# InkTime_Schematic.net
KiCad netlist of a schematic drawn in EAGLE
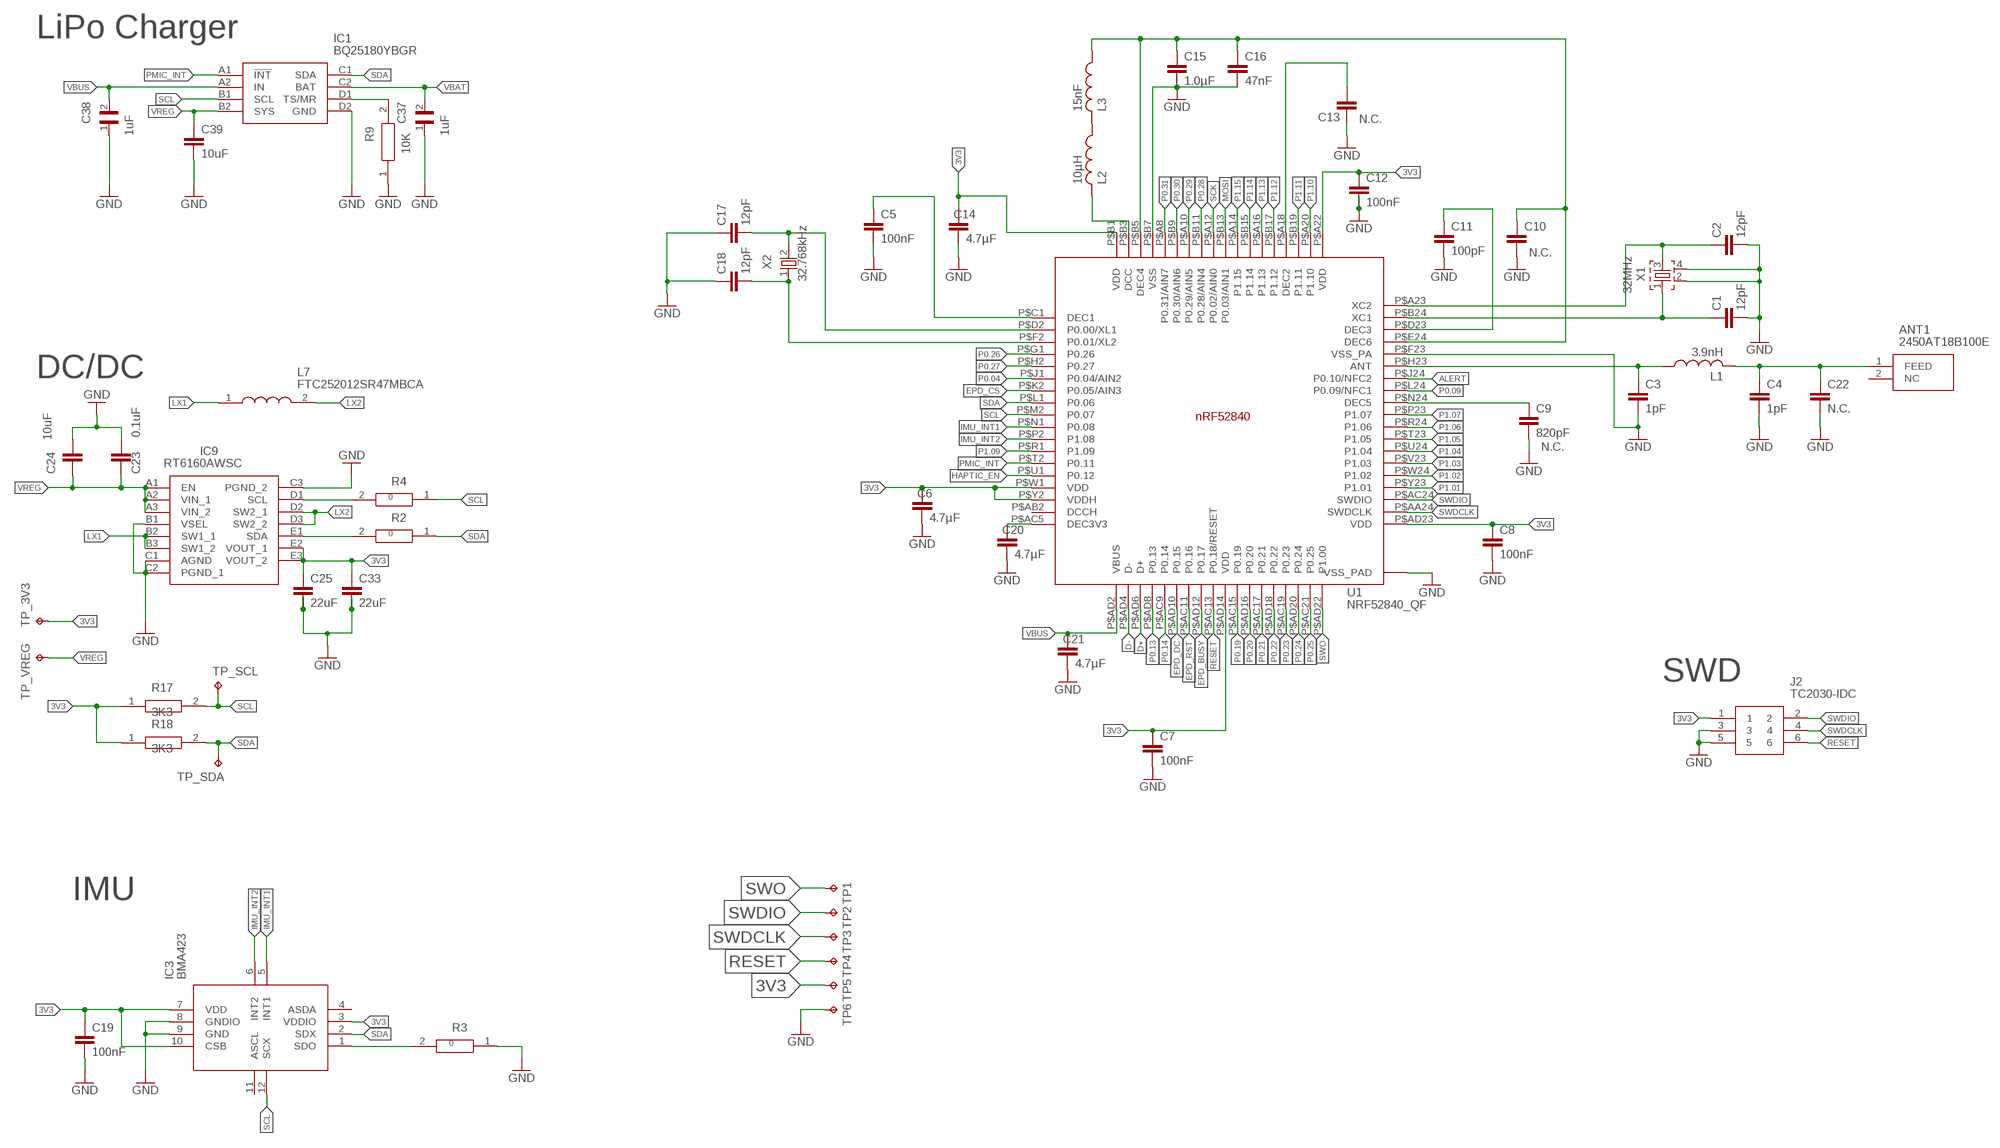
[diagram p0: schematic, sheet 1, part 1 of 2]
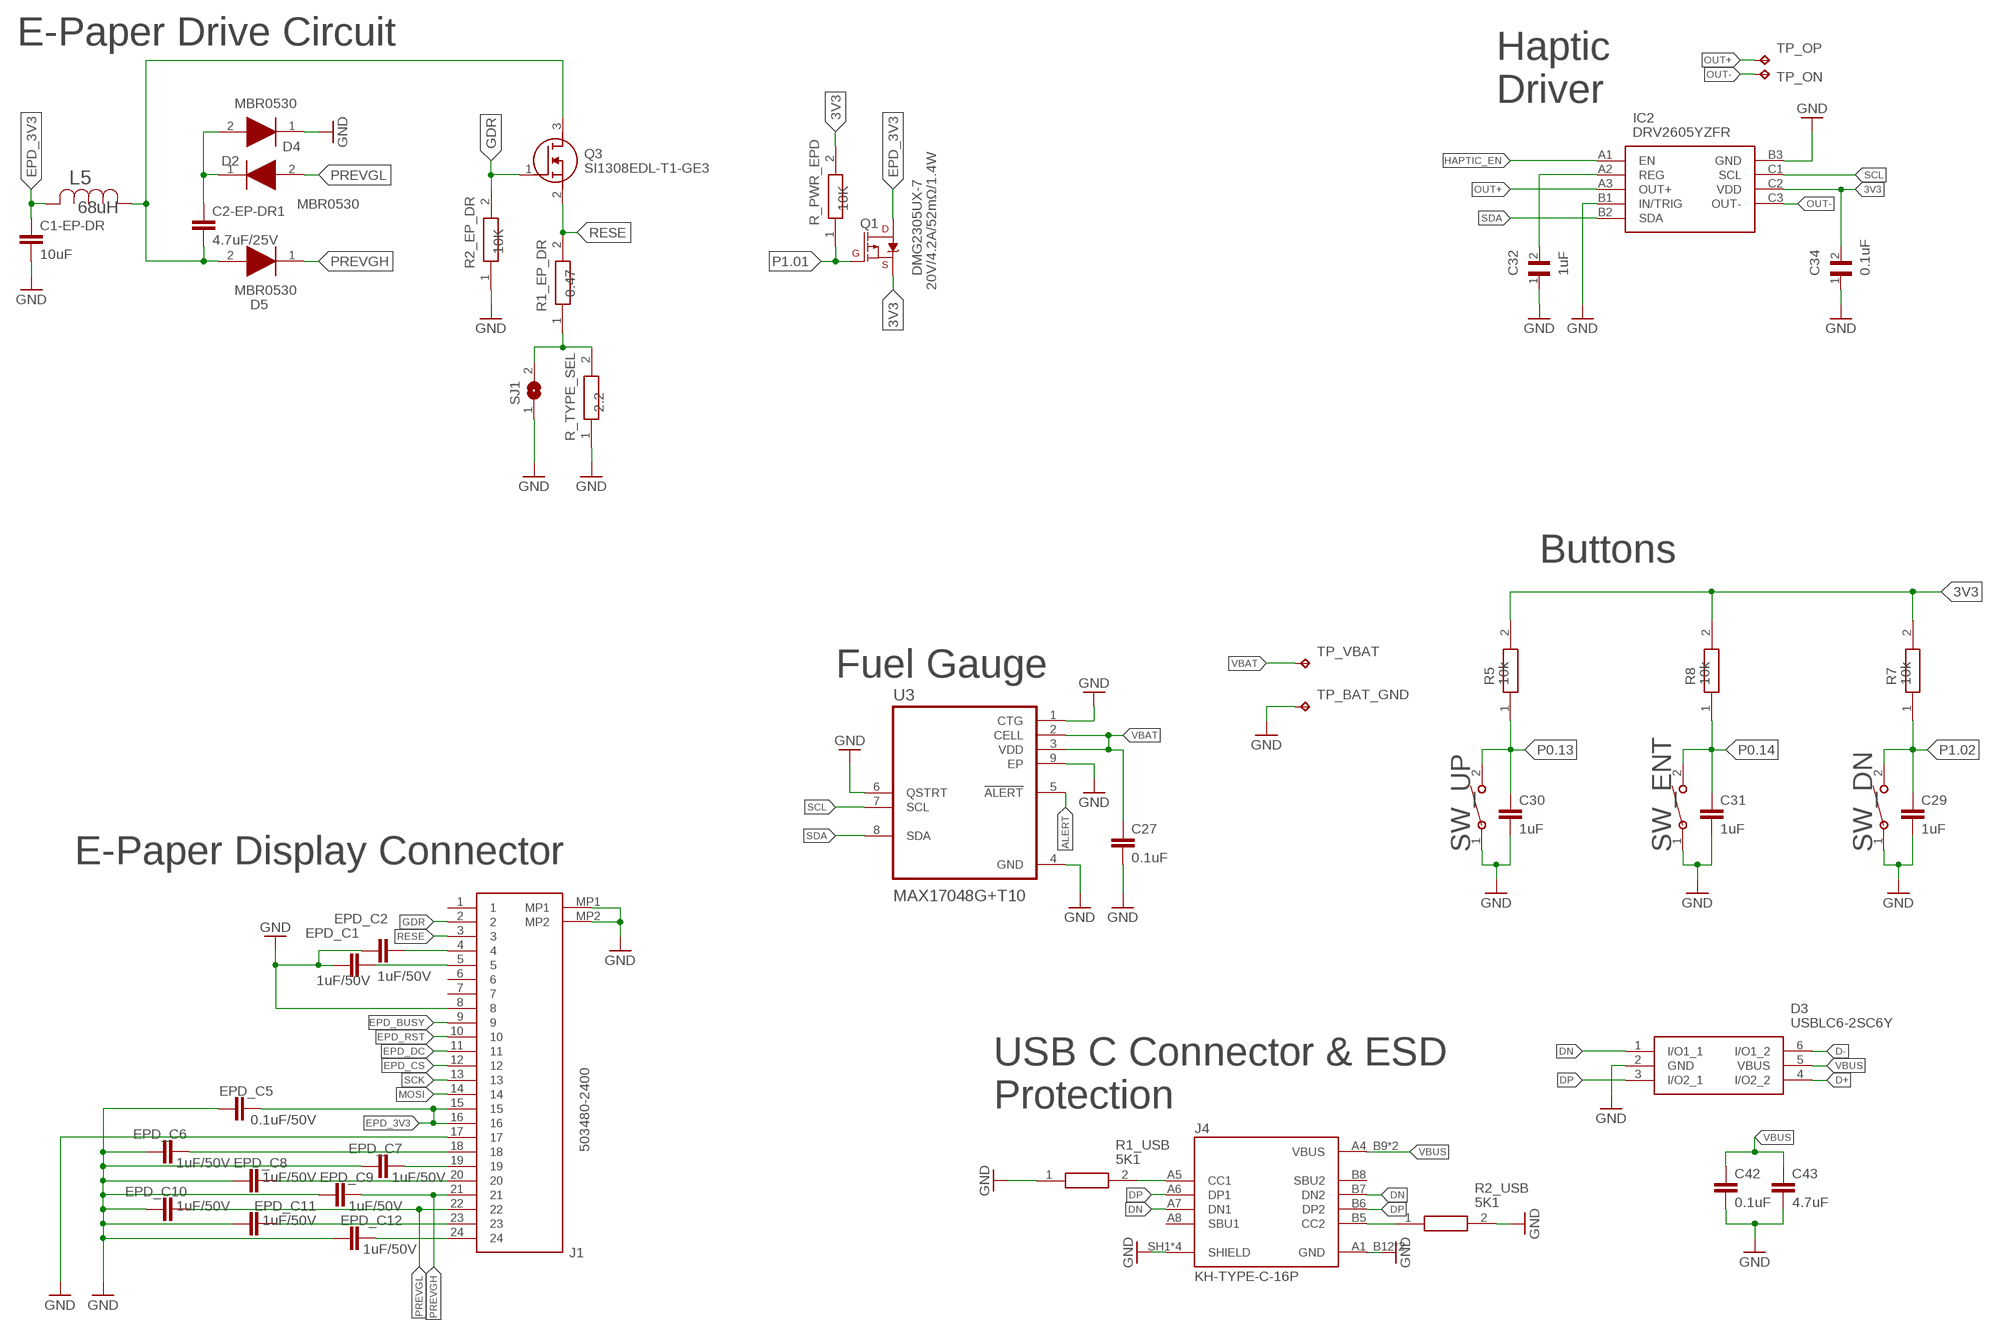
[diagram p1: schematic, sheet 1, part 2 of 2]

(export (version "E")
  (design (tool "Eeschema 10.0.6"))
  (components
    (comp (ref "ANT1")
      (value "2450AT18B100E")
      (footprint "eagle-import:2450AT18B100E_ANTC3216X140N")
      (fields (field (name "MOUSER_PART_NUMBER") "609-2450AT18B100E"))
      (libsource (lib "eagle-import") (part "2450AT18B100E_2450AT18B100E"))
    )
    (comp (ref "C1")
      (value "12pF")
      (footprint "eagle-import:NORDIC_NRF_3_RESC0201_L")
      (libsource (lib "eagle-import") (part "NORDIC_NRF_3_CAPACITOR_0201_L"))
    )
    (comp (ref "C1-EP-DR")
      (value "10uF")
      (footprint "eagle-import:NORDIC_NRF_3_RESC0402_L")
      (libsource (lib "eagle-import") (part "NORDIC_NRF_3_CAPACITOR_0402_L"))
    )
    (comp (ref "C2")
      (value "12pF")
      (footprint "eagle-import:NORDIC_NRF_3_RESC0201_L")
      (libsource (lib "eagle-import") (part "NORDIC_NRF_3_CAPACITOR_0201_L"))
    )
    (comp (ref "C2-EP-DR1")
      (value "4.7uF/25V")
      (footprint "eagle-import:NORDIC_NRF_3_RESC0402_L")
      (libsource (lib "eagle-import") (part "NORDIC_NRF_3_CAPACITOR_0402_L"))
    )
    (comp (ref "C3")
      (value "1pF")
      (footprint "eagle-import:NORDIC_NRF_3_RESC0201_L")
      (libsource (lib "eagle-import") (part "NORDIC_NRF_3_CAPACITOR_0201_L"))
    )
    (comp (ref "C4")
      (value "1pF")
      (footprint "eagle-import:NORDIC_NRF_3_RESC0201_L")
      (libsource (lib "eagle-import") (part "NORDIC_NRF_3_CAPACITOR_0201_L"))
    )
    (comp (ref "C5")
      (value "100nF")
      (footprint "eagle-import:NORDIC_NRF_3_RESC0201_L")
      (libsource (lib "eagle-import") (part "NORDIC_NRF_3_CAPACITOR_0201_L"))
    )
    (comp (ref "C6")
      (value "4.7µF")
      (footprint "eagle-import:NORDIC_NRF_3_RESC0402_L")
      (libsource (lib "eagle-import") (part "NORDIC_NRF_3_CAPACITOR_0402_L"))
    )
    (comp (ref "C7")
      (value "100nF")
      (footprint "eagle-import:NORDIC_NRF_3_RESC0201_L")
      (libsource (lib "eagle-import") (part "NORDIC_NRF_3_CAPACITOR_0201_L"))
    )
    (comp (ref "C8")
      (value "100nF")
      (footprint "eagle-import:NORDIC_NRF_3_RESC0201_L")
      (libsource (lib "eagle-import") (part "NORDIC_NRF_3_CAPACITOR_0201_L"))
    )
    (comp (ref "C9")
      (value "820pF")
      (footprint "eagle-import:NORDIC_NRF_3_RESC0201_L")
      (libsource (lib "eagle-import") (part "NORDIC_NRF_3_CAPACITOR_0201_L"))
    )
    (comp (ref "C10")
      (value "NORDIC_NRF_3_CAPACITOR_0201_L")
      (footprint "eagle-import:NORDIC_NRF_3_RESC0201_L")
      (libsource (lib "eagle-import") (part "NORDIC_NRF_3_CAPACITOR_0201_L"))
    )
    (comp (ref "C11")
      (value "100pF")
      (footprint "eagle-import:NORDIC_NRF_3_RESC0201_L")
      (libsource (lib "eagle-import") (part "NORDIC_NRF_3_CAPACITOR_0201_L"))
    )
    (comp (ref "C12")
      (value "100nF")
      (footprint "eagle-import:NORDIC_NRF_3_RESC0201_L")
      (libsource (lib "eagle-import") (part "NORDIC_NRF_3_CAPACITOR_0201_L"))
    )
    (comp (ref "C13")
      (value "NORDIC_NRF_3_CAPACITOR_0201_L")
      (footprint "eagle-import:NORDIC_NRF_3_RESC0201_L")
      (libsource (lib "eagle-import") (part "NORDIC_NRF_3_CAPACITOR_0201_L"))
    )
    (comp (ref "C14")
      (value "4.7µF")
      (footprint "eagle-import:NORDIC_NRF_3_RESC0402_L")
      (libsource (lib "eagle-import") (part "NORDIC_NRF_3_CAPACITOR_0402_L"))
    )
    (comp (ref "C15")
      (value "1.0µF")
      (footprint "eagle-import:NORDIC_NRF_3_RESC0402_L")
      (libsource (lib "eagle-import") (part "NORDIC_NRF_3_CAPACITOR_0402_L"))
    )
    (comp (ref "C16")
      (value "47nF")
      (footprint "eagle-import:NORDIC_NRF_3_RESC0201_L")
      (libsource (lib "eagle-import") (part "NORDIC_NRF_3_CAPACITOR_0201_L"))
    )
    (comp (ref "C17")
      (value "12pF")
      (footprint "eagle-import:NORDIC_NRF_3_RESC0201_L")
      (libsource (lib "eagle-import") (part "NORDIC_NRF_3_CAPACITOR_0201_L"))
    )
    (comp (ref "C18")
      (value "12pF")
      (footprint "eagle-import:NORDIC_NRF_3_RESC0201_L")
      (libsource (lib "eagle-import") (part "NORDIC_NRF_3_CAPACITOR_0201_L"))
    )
    (comp (ref "C19")
      (value "100nF")
      (footprint "eagle-import:NORDIC_NRF_3_RESC0201_L")
      (libsource (lib "eagle-import") (part "InkTime_v5_vf.fkz7WSyWSr61TWkXU9X4_w_NORDIC_NRF_3_CAPACITOR_0201_L"))
    )
    (comp (ref "C20")
      (value "4.7µF")
      (footprint "eagle-import:NORDIC_NRF_3_RESC0402_L")
      (libsource (lib "eagle-import") (part "NORDIC_NRF_3_CAPACITOR_0402_L"))
    )
    (comp (ref "C21")
      (value "4.7µF")
      (footprint "eagle-import:NORDIC_NRF_3_RESC0402_L")
      (libsource (lib "eagle-import") (part "NORDIC_NRF_3_CAPACITOR_0402_L"))
    )
    (comp (ref "C22")
      (value "N.C.")
      (footprint "eagle-import:NORDIC_NRF_3_RESC0201_L")
      (libsource (lib "eagle-import") (part "NORDIC_NRF_3_CAPACITOR_0201_L"))
    )
    (comp (ref "C23")
      (value "0.1uF")
      (footprint "eagle-import:NORDIC_NRF_3_RESC0201_L")
      (libsource (lib "eagle-import") (part "InkTime_v5_vf.fkz7WSyWSr61TWkXU9X4_w_NORDIC_NRF_3_CAPACITOR_0201_L"))
    )
    (comp (ref "C24")
      (value "10uF")
      (footprint "eagle-import:NORDIC_NRF_3_RESC0402_L")
      (libsource (lib "eagle-import") (part "NORDIC_NRF_3_CAPACITOR_0402_L"))
    )
    (comp (ref "C25")
      (value "22uF")
      (footprint "eagle-import:NORDIC_NRF_3_RESC0402_L")
      (libsource (lib "eagle-import") (part "NORDIC_NRF_3_CAPACITOR_0402_L"))
    )
    (comp (ref "C27")
      (value "0.1uF")
      (footprint "eagle-import:NORDIC_NRF_3_RESC0201_L")
      (libsource (lib "eagle-import") (part "InkTime_v5_vf.fkz7WSyWSr61TWkXU9X4_w_NORDIC_NRF_3_CAPACITOR_0201_L"))
    )
    (comp (ref "C29")
      (value "1uF")
      (footprint "eagle-import:NORDIC_NRF_3_RESC0402_L")
      (libsource (lib "eagle-import") (part "InkTime_v5_vf.fkz7WSyWSr61TWkXU9X4_w_NORDIC_NRF_3_CAPACITOR_0402_L"))
    )
    (comp (ref "C30")
      (value "1uF")
      (footprint "eagle-import:NORDIC_NRF_3_RESC0402_L")
      (libsource (lib "eagle-import") (part "InkTime_v5_vf.fkz7WSyWSr61TWkXU9X4_w_NORDIC_NRF_3_CAPACITOR_0402_L"))
    )
    (comp (ref "C31")
      (value "1uF")
      (footprint "eagle-import:NORDIC_NRF_3_RESC0402_L")
      (libsource (lib "eagle-import") (part "InkTime_v5_vf.fkz7WSyWSr61TWkXU9X4_w_NORDIC_NRF_3_CAPACITOR_0402_L"))
    )
    (comp (ref "C32")
      (value "1uF")
      (footprint "eagle-import:GRM011R60J152KE01L_2_CAPC0201X13N")
      (fields (field (name "MF") "Murata") (field (name "MP") "GRM011R60J152KE01L"))
      (libsource (lib "eagle-import") (part "GRM011R60J152KE01L_2_GRM011R60J152KE01L"))
    )
    (comp (ref "C33")
      (value "22uF")
      (footprint "eagle-import:NORDIC_NRF_3_RESC0402_L")
      (libsource (lib "eagle-import") (part "NORDIC_NRF_3_CAPACITOR_0402_L"))
    )
    (comp (ref "C34")
      (value "0.1uF")
      (footprint "eagle-import:GRM011R60J152KE01L_2_CAPC0201X13N")
      (fields (field (name "MF") "Murata") (field (name "MP") "GRM011R60J152KE01L"))
      (libsource (lib "eagle-import") (part "GRM011R60J152KE01L_2_GRM011R60J152KE01L"))
    )
    (comp (ref "C37")
      (value "1uF")
      (footprint "eagle-import:GRM011R60J152KE01L_2_CAPC0201X13N")
      (fields (field (name "MF") "Murata") (field (name "MP") "GRM011R60J152KE01L"))
      (libsource (lib "eagle-import") (part "GRM011R60J152KE01L_2_GRM011R60J152KE01L"))
    )
    (comp (ref "C38")
      (value "1uF")
      (footprint "eagle-import:GRM011R60J152KE01L_2_CAPC0201X13N")
      (fields (field (name "MF") "Murata") (field (name "MP") "GRM011R60J152KE01L"))
      (libsource (lib "eagle-import") (part "GRM011R60J152KE01L_2_GRM011R60J152KE01L"))
    )
    (comp (ref "C39")
      (value "10uF")
      (footprint "eagle-import:NORDIC_NRF_3_RESC0402_L")
      (libsource (lib "eagle-import") (part "NORDIC_NRF_3_CAPACITOR_0402_L"))
    )
    (comp (ref "C42")
      (value "0.1uF")
      (footprint "eagle-import:NORDIC_NRF_3_RESC0201_L")
      (libsource (lib "eagle-import") (part "InkTime_v5_vf.fkz7WSyWSr61TWkXU9X4_w_NORDIC_NRF_3_CAPACITOR_0201_L"))
    )
    (comp (ref "C43")
      (value "4.7uF")
      (footprint "eagle-import:NORDIC_NRF_3_RESC0402_L")
      (libsource (lib "eagle-import") (part "InkTime_v5_vf.fkz7WSyWSr61TWkXU9X4_w_NORDIC_NRF_3_CAPACITOR_0402_L"))
    )
    (comp (ref "D2")
      (value "MBR0530")
      (footprint "eagle-import:ESP32_C6_LIBRARY_5_SOD3716X135N")
      (fields (field (name "MF") "ON Semiconductor"))
      (libsource (lib "eagle-import") (part "ESP32_C6_LIBRARY_5_MBR0530"))
    )
    (comp (ref "D3")
      (value "USBLC6-2SC6Y")
      (footprint "eagle-import:ESP32_C6_LIBRARY_3_SOT95P280X145-6N")
      (fields (field (name "MF") "STMicroelectronics"))
      (libsource (lib "eagle-import") (part "ESP32_C6_LIBRARY_3_USBLC6-2SC6Y"))
    )
    (comp (ref "D4")
      (value "MBR0530")
      (footprint "eagle-import:ESP32_C6_LIBRARY_5_SOD3716X135N")
      (fields (field (name "MF") "ON Semiconductor"))
      (libsource (lib "eagle-import") (part "ESP32_C6_LIBRARY_5_MBR0530"))
    )
    (comp (ref "D5")
      (value "MBR0530")
      (footprint "eagle-import:ESP32_C6_LIBRARY_5_SOD3716X135N")
      (fields (field (name "MF") "ON Semiconductor"))
      (libsource (lib "eagle-import") (part "ESP32_C6_LIBRARY_5_MBR0530"))
    )
    (comp (ref "EPD_C1")
      (value "1uF/50V")
      (footprint "eagle-import:NORDIC_NRF_3_RESC0402_L")
      (libsource (lib "eagle-import") (part "InkTime_v5_vf.fkz7WSyWSr61TWkXU9X4_w_NORDIC_NRF_3_CAPACITOR_0402_L"))
    )
    (comp (ref "EPD_C2")
      (value "1uF/50V")
      (footprint "eagle-import:NORDIC_NRF_3_RESC0402_L")
      (libsource (lib "eagle-import") (part "InkTime_v5_vf.fkz7WSyWSr61TWkXU9X4_w_NORDIC_NRF_3_CAPACITOR_0402_L"))
    )
    (comp (ref "EPD_C5")
      (value "0.1uF/50V")
      (footprint "eagle-import:NORDIC_NRF_3_RESC0201_L")
      (libsource (lib "eagle-import") (part "InkTime_v5_vf.fkz7WSyWSr61TWkXU9X4_w_NORDIC_NRF_3_CAPACITOR_0201_L"))
    )
    (comp (ref "EPD_C6")
      (value "1uF/50V")
      (footprint "eagle-import:NORDIC_NRF_3_RESC0402_L")
      (libsource (lib "eagle-import") (part "InkTime_v5_vf.fkz7WSyWSr61TWkXU9X4_w_NORDIC_NRF_3_CAPACITOR_0402_L"))
    )
    (comp (ref "EPD_C7")
      (value "1uF/50V")
      (footprint "eagle-import:NORDIC_NRF_3_RESC0402_L")
      (libsource (lib "eagle-import") (part "InkTime_v5_vf.fkz7WSyWSr61TWkXU9X4_w_NORDIC_NRF_3_CAPACITOR_0402_L"))
    )
    (comp (ref "EPD_C8")
      (value "1uF/50V")
      (footprint "eagle-import:NORDIC_NRF_3_RESC0402_L")
      (libsource (lib "eagle-import") (part "InkTime_v5_vf.fkz7WSyWSr61TWkXU9X4_w_NORDIC_NRF_3_CAPACITOR_0402_L"))
    )
    (comp (ref "EPD_C9")
      (value "1uF/50V")
      (footprint "eagle-import:NORDIC_NRF_3_RESC0402_L")
      (libsource (lib "eagle-import") (part "InkTime_v5_vf.fkz7WSyWSr61TWkXU9X4_w_NORDIC_NRF_3_CAPACITOR_0402_L"))
    )
    (comp (ref "EPD_C10")
      (value "1uF/50V")
      (footprint "eagle-import:NORDIC_NRF_3_RESC0402_L")
      (libsource (lib "eagle-import") (part "InkTime_v5_vf.fkz7WSyWSr61TWkXU9X4_w_NORDIC_NRF_3_CAPACITOR_0402_L"))
    )
    (comp (ref "EPD_C11")
      (value "1uF/50V")
      (footprint "eagle-import:NORDIC_NRF_3_RESC0402_L")
      (libsource (lib "eagle-import") (part "InkTime_v5_vf.fkz7WSyWSr61TWkXU9X4_w_NORDIC_NRF_3_CAPACITOR_0402_L"))
    )
    (comp (ref "EPD_C12")
      (value "1uF/50V")
      (footprint "eagle-import:NORDIC_NRF_3_RESC0402_L")
      (libsource (lib "eagle-import") (part "InkTime_v5_vf.fkz7WSyWSr61TWkXU9X4_w_NORDIC_NRF_3_CAPACITOR_0402_L"))
    )
    (comp (ref "IC1")
      (value "BQ25180YBGR")
      (footprint "eagle-import:BQ25180YBGR_BGA8C40P2X4_100X155X50")
      (fields (field (name "MOUSER_PART_NUMBER") "595-BQ25180YBGR"))
      (libsource (lib "eagle-import") (part "BQ25180YBGR_BQ25180YBGR"))
    )
    (comp (ref "IC2")
      (value "DRV2605YZFR")
      (footprint "eagle-import:DRV2605YZFR_BGA9C50P3X3_144X144X62")
      (libsource (lib "eagle-import") (part "DRV2605YZFR_DRV2605YZFR"))
    )
    (comp (ref "IC3")
      (value "BMA423")
      (footprint "eagle-import:BMA423_BMA423")
      (fields (field (name "MOUSER_PART_NUMBER") "262-BMA423"))
      (libsource (lib "eagle-import") (part "BMA423_BMA423"))
    )
    (comp (ref "IC9")
      (value "RT6160AWSC")
      (footprint "eagle-import:RT6160AWSC_BGA15C40P3X5_140X230X60")
      (fields (field (name "MOUSER_PART_NUMBER") "835-RT6160AWSC"))
      (libsource (lib "eagle-import") (part "RT6160AWSC_RT6160AWSC"))
    )
    (comp (ref "J1")
      (value "503480-2400")
      (footprint "eagle-import:503480-2400_5034802400")
      (fields (field (name "MOUSER_PART_NUMBER") "538-503480-2400"))
      (libsource (lib "eagle-import") (part "503480-2400_503480-2400"))
    )
    (comp (ref "J2")
      (value "TC2030-IDC")
      (footprint "eagle-import:TC2030-IDC_TC2030IDC")
      (libsource (lib "eagle-import") (part "TC2030-IDC_TC2030-IDC"))
    )
    (comp (ref "J4")
      (value "KH-TYPE-C-16P")
      (footprint "eagle-import:KH-TYPE-C-16P_KINGHELM_KH-TYPE-C-16P")
      (fields (field (name "MF") "kinghelm"))
      (libsource (lib "eagle-import") (part "KH-TYPE-C-16P_KH-TYPE-C-16P"))
    )
    (comp (ref "L1")
      (value "3.9nH")
      (footprint "eagle-import:NORDIC_NRF_2_RESC0402_L")
      (libsource (lib "eagle-import") (part "InkTime_v5_vf.fkz7WSyWSr61TWkXU9X4_w_NORDIC_NRF_2_INDUCTOR_0402_L"))
    )
    (comp (ref "L2")
      (value "10µH")
      (footprint "eagle-import:NORDIC_NRF_2_RESC0402_L")
      (libsource (lib "eagle-import") (part "NORDIC_NRF_2_INDUCTOR_0402_L"))
    )
    (comp (ref "L3")
      (value "15nF")
      (footprint "eagle-import:NORDIC_NRF_2_RESC0402_L")
      (libsource (lib "eagle-import") (part "NORDIC_NRF_2_INDUCTOR_0402_L"))
    )
    (comp (ref "L5")
      (value "68uH")
      (footprint "eagle-import:ESP32_C6_LIBRARY_2_IND_4828-WE-TPC_WRE")
      (fields
        (field (name "MANUFACTURER_PART_NUMBER") "744043680")
        (field (name "COPYRIGHT") "Copyright (C) 2024 Ultra Librarian. All rights reserved.")
      )
      (libsource (lib "eagle-import") (part "ESP32_C6_LIBRARY_2_744043680IND_4828-WE-TPC_WRE"))
    )
    (comp (ref "L7")
      (value "FTC252012SR47MBCA")
      (footprint "eagle-import:MLP2016SR47MT0S1_INDC2016X100N")
      (libsource (lib "eagle-import") (part "MLP2016SR47MT0S1_FTC252012SR47MBCA"))
    )
    (comp (ref "Q1")
      (value "20V/4.2A/52mΩ/1.4W")
      (footprint "eagle-import:ESP32_C6_LIBRARY_4_ESP32_C6_LIBRARY_4_ESP32_C6_LIBRARY_4_ESP32_C6_LIBRARY_4_ESP32_WROVER_SPARKFUN-DISCRETESEMI_SOT23-3")
      (libsource (lib "eagle-import") (part "ESP32_C6_LIBRARY_4_ESP32_WROVER_SPARKFUN-DISCRETESEMI_MOSFET_PCH-DMG2305UX-7"))
    )
    (comp (ref "Q3")
      (value "SI1308EDL-T1-GE3")
      (footprint "eagle-import:ESP32_C6_LIBRARY_6_SOT65P210X110-3N")
      (fields (field (name "MF") "Vishay Siliconix"))
      (libsource (lib "eagle-import") (part "ESP32_C6_LIBRARY_6_SI1308EDL-T1-GE3"))
    )
    (comp (ref "R1_EP_DR")
      (value "0.47")
      (footprint "eagle-import:CPF0201D7K68C1_0201")
      (libsource (lib "eagle-import") (part "CPF0201D7K68C1_CPF0201D7K68C1"))
    )
    (comp (ref "R1_USB")
      (value "5K1")
      (footprint "eagle-import:ERA-1AEB3401C_0201")
      (libsource (lib "eagle-import") (part "ERA-1AEB3401C_CPF0201D7K68C1"))
    )
    (comp (ref "R2")
      (value "CPF0201D7K68C1_CPF0201D7K68C1")
      (footprint "eagle-import:CPF0201D7K68C1_0201")
      (libsource (lib "eagle-import") (part "CPF0201D7K68C1_CPF0201D7K68C1"))
    )
    (comp (ref "R2_EP_DR")
      (value "10K")
      (footprint "eagle-import:CPF0201D7K68C1_0201")
      (libsource (lib "eagle-import") (part "CPF0201D7K68C1_CPF0201D7K68C1"))
    )
    (comp (ref "R2_USB")
      (value "5K1")
      (footprint "eagle-import:ERA-1AEB3401C_0201")
      (libsource (lib "eagle-import") (part "ERA-1AEB3401C_CPF0201D7K68C1"))
    )
    (comp (ref "R3")
      (value "CPF0201D7K68C1_CPF0201D7K68C1")
      (footprint "eagle-import:CPF0201D7K68C1_0201")
      (libsource (lib "eagle-import") (part "CPF0201D7K68C1_CPF0201D7K68C1"))
    )
    (comp (ref "R4")
      (value "CPF0201D7K68C1_CPF0201D7K68C1")
      (footprint "eagle-import:CPF0201D7K68C1_0201")
      (libsource (lib "eagle-import") (part "CPF0201D7K68C1_CPF0201D7K68C1"))
    )
    (comp (ref "R5")
      (value "10k")
      (footprint "eagle-import:CPF0201D7K68C1_0201")
      (libsource (lib "eagle-import") (part "InkTime_v5_vf.fkz7WSyWSr61TWkXU9X4_w_CPF0201D7K68C1_CPF0201D7K68C1"))
    )
    (comp (ref "R7")
      (value "10k")
      (footprint "eagle-import:CPF0201D7K68C1_0201")
      (libsource (lib "eagle-import") (part "InkTime_v5_vf.fkz7WSyWSr61TWkXU9X4_w_CPF0201D7K68C1_CPF0201D7K68C1"))
    )
    (comp (ref "R8")
      (value "10k")
      (footprint "eagle-import:CPF0201D7K68C1_0201")
      (libsource (lib "eagle-import") (part "InkTime_v5_vf.fkz7WSyWSr61TWkXU9X4_w_CPF0201D7K68C1_CPF0201D7K68C1"))
    )
    (comp (ref "R9")
      (value "10K")
      (footprint "eagle-import:CPF0201D7K68C1_0201")
      (libsource (lib "eagle-import") (part "CPF0201D7K68C1_CPF0201D7K68C1"))
    )
    (comp (ref "R17")
      (value "3K3")
      (footprint "eagle-import:CPF0201D7K68C1_0201")
      (libsource (lib "eagle-import") (part "CPF0201D7K68C1_CPF0201D7K68C1"))
    )
    (comp (ref "R18")
      (value "3K3")
      (footprint "eagle-import:CPF0201D7K68C1_0201")
      (libsource (lib "eagle-import") (part "CPF0201D7K68C1_CPF0201D7K68C1"))
    )
    (comp (ref "R_PWR_EPD")
      (value "10K")
      (footprint "eagle-import:CPF0201D7K68C1_0201")
      (libsource (lib "eagle-import") (part "CPF0201D7K68C1_CPF0201D7K68C1"))
    )
    (comp (ref "R_TYPE_SEL")
      (value "2.2")
      (footprint "eagle-import:CPF0201D7K68C1_0201")
      (libsource (lib "eagle-import") (part "CPF0201D7K68C1_CPF0201D7K68C1"))
    )
    (comp (ref "SJ1")
      (value "ESP32_C6_LIBRARY_7_JUMPER_SJ")
      (footprint "eagle-import:ESP32_C6_LIBRARY_7_JUMPER_SJ")
      (libsource (lib "eagle-import") (part "ESP32_C6_LIBRARY_7_JUMPER_SJ"))
    )
    (comp (ref "SW_DN")
      (value "2025-10-22_07-23-44_LIBRARY_EVP-AKE31ASW_EVP-AKE31A_PAN")
      (footprint "eagle-import:2025-10-22_07-23-44_LIBRARY_SW_EVP-AKE31A_PAN")
      (fields
        (field (name "MANUFACTURER_PART_NUMBER") "EVP-AKE31A")
        (field (name "COPYRIGHT") "Copyright (C) 2025 Ultra Librarian. All rights reserved.")
      )
      (libsource (lib "eagle-import") (part "2025-10-22_07-23-44_LIBRARY_EVP-AKE31ASW_EVP-AKE31A_PAN"))
    )
    (comp (ref "SW_ENT")
      (value "SW_ENT")
      (footprint "eagle-import:2025-10-22_07-23-44_LIBRARY_SW_EVP-AKE31A_PAN")
      (fields
        (field (name "MANUFACTURER_PART_NUMBER") "EVP-AKE31A")
        (field (name "COPYRIGHT") "Copyright (C) 2025 Ultra Librarian. All rights reserved.")
      )
      (libsource (lib "eagle-import") (part "2025-10-22_07-23-44_LIBRARY_EVP-AKE31ASW_EVP-AKE31A_PAN"))
    )
    (comp (ref "SW_UP")
      (value "2025-10-22_07-23-44_LIBRARY_EVP-AKE31ASW_EVP-AKE31A_PAN")
      (footprint "eagle-import:2025-10-22_07-23-44_LIBRARY_SW_EVP-AKE31A_PAN")
      (fields
        (field (name "MANUFACTURER_PART_NUMBER") "EVP-AKE31A")
        (field (name "COPYRIGHT") "Copyright (C) 2025 Ultra Librarian. All rights reserved.")
      )
      (libsource (lib "eagle-import") (part "2025-10-22_07-23-44_LIBRARY_EVP-AKE31ASW_EVP-AKE31A_PAN"))
    )
    (comp (ref "TP1")
      (value "HECTOR_WATCH_1_TPTP20R")
      (footprint "eagle-import:HECTOR_WATCH_1_TP20R")
      (libsource (lib "eagle-import") (part "HECTOR_WATCH_1_TPTP20R"))
    )
    (comp (ref "TP2")
      (value "HECTOR_WATCH_1_TPTP20R")
      (footprint "eagle-import:HECTOR_WATCH_1_TP20R")
      (libsource (lib "eagle-import") (part "HECTOR_WATCH_1_TPTP20R"))
    )
    (comp (ref "TP3")
      (value "HECTOR_WATCH_1_TPTP20R")
      (footprint "eagle-import:HECTOR_WATCH_1_TP20R")
      (libsource (lib "eagle-import") (part "HECTOR_WATCH_1_TPTP20R"))
    )
    (comp (ref "TP4")
      (value "HECTOR_WATCH_1_TPTP20R")
      (footprint "eagle-import:HECTOR_WATCH_1_TP20R")
      (libsource (lib "eagle-import") (part "HECTOR_WATCH_1_TPTP20R"))
    )
    (comp (ref "TP5")
      (value "HECTOR_WATCH_1_TPTP20R")
      (footprint "eagle-import:HECTOR_WATCH_1_TP20R")
      (libsource (lib "eagle-import") (part "HECTOR_WATCH_1_TPTP20R"))
    )
    (comp (ref "TP6")
      (value "HECTOR_WATCH_1_TPTP20R")
      (footprint "eagle-import:HECTOR_WATCH_1_TP20R")
      (libsource (lib "eagle-import") (part "HECTOR_WATCH_1_TPTP20R"))
    )
    (comp (ref "TP_3V3")
      (value "HECTOR_WATCH_1_TPTP20R")
      (footprint "eagle-import:HECTOR_WATCH_1_TP20R")
      (libsource (lib "eagle-import") (part "HECTOR_WATCH_1_TPTP20R"))
    )
    (comp (ref "TP_BAT_GND")
      (value "HECTOR_WATCH_1_TPTP20R")
      (footprint "eagle-import:HECTOR_WATCH_1_TP20R")
      (libsource (lib "eagle-import") (part "InkTime_v5_vf.fkz7WSyWSr61TWkXU9X4_w_HECTOR_WATCH_1_TPTP20R"))
    )
    (comp (ref "TP_ON")
      (value "HECTOR_WATCH_1_TPTP20R")
      (footprint "eagle-import:HECTOR_WATCH_1_TP20R")
      (libsource (lib "eagle-import") (part "HECTOR_WATCH_1_TPTP20R"))
    )
    (comp (ref "TP_OP")
      (value "HECTOR_WATCH_1_TPTP20R")
      (footprint "eagle-import:HECTOR_WATCH_1_TP20R")
      (libsource (lib "eagle-import") (part "HECTOR_WATCH_1_TPTP20R"))
    )
    (comp (ref "TP_SCL")
      (value "HECTOR_WATCH_1_TPTP20R")
      (footprint "eagle-import:HECTOR_WATCH_1_TP20R")
      (libsource (lib "eagle-import") (part "HECTOR_WATCH_1_TPTP20R"))
    )
    (comp (ref "TP_SDA")
      (value "HECTOR_WATCH_1_TPTP20R")
      (footprint "eagle-import:HECTOR_WATCH_1_TP20R")
      (libsource (lib "eagle-import") (part "HECTOR_WATCH_1_TPTP20R"))
    )
    (comp (ref "TP_VBAT")
      (value "HECTOR_WATCH_1_TPTP20R")
      (footprint "eagle-import:HECTOR_WATCH_1_TP20R")
      (libsource (lib "eagle-import") (part "InkTime_v5_vf.fkz7WSyWSr61TWkXU9X4_w_HECTOR_WATCH_1_TPTP20R"))
    )
    (comp (ref "TP_VREG")
      (value "HECTOR_WATCH_1_TPTP20R")
      (footprint "eagle-import:HECTOR_WATCH_1_TP20R")
      (libsource (lib "eagle-import") (part "HECTOR_WATCH_1_TPTP20R"))
    )
    (comp (ref "U1")
      (value "NRF52840_QF")
      (footprint "eagle-import:NORDIC_NRF_4_AQFN50P700X700X85_HS-74N")
      (libsource (lib "eagle-import") (part "NORDIC_NRF_4_NRF52840_QF"))
    )
    (comp (ref "U3")
      (value "MAX17048G+T10")
      (footprint "eagle-import:ESP32_C6_LIBRARY_SON50P200X200X80-9N")
      (fields (field (name "MF") "Analog Devices"))
      (libsource (lib "eagle-import") (part "ESP32_C6_LIBRARY_MAX17048G+T10"))
    )
    (comp (ref "X1")
      (value "32MHz")
      (footprint "eagle-import:NORDIC_NRF_BT-XTAL_2016_N")
      (libsource (lib "eagle-import") (part "NORDIC_NRF_XTAL_32MHZ"))
    )
    (comp (ref "X2")
      (value "32.768kHz")
      (footprint "eagle-import:NORDIC_NRF_1_XTAL_3215_N")
      (libsource (lib "eagle-import") (part "NORDIC_NRF_1_XTAL_32KHZ"))
    )
  )
  (nets
    (net (code "1") (name "3V3") (class "Default")
      (node (ref "C12") (pin "1") (pinfunction "1_1") (pintype "passive"))
      (node (ref "C14") (pin "1") (pinfunction "1_1") (pintype "passive"))
      (node (ref "C19") (pin "1") (pinfunction "1_1") (pintype "passive"))
      (node (ref "C25") (pin "1") (pinfunction "1_1") (pintype "passive"))
      (node (ref "C33") (pin "1") (pinfunction "1_1") (pintype "passive"))
      (node (ref "C34") (pin "2") (pinfunction "2_2") (pintype "passive"))
      (node (ref "C6") (pin "1") (pinfunction "1_1") (pintype "passive"))
      (node (ref "C7") (pin "1") (pinfunction "1_1") (pintype "passive"))
      (node (ref "C8") (pin "1") (pinfunction "1_1") (pintype "passive"))
      (node (ref "IC2") (pin "C2") (pinfunction "VDD_C2") (pintype "bidirectional"))
      (node (ref "IC3") (pin "10") (pinfunction "CSB_10") (pintype "bidirectional"))
      (node (ref "IC3") (pin "3") (pinfunction "VDDIO_3") (pintype "bidirectional"))
      (node (ref "IC3") (pin "7") (pinfunction "VDD_7") (pintype "bidirectional"))
      (node (ref "IC9") (pin "E2") (pinfunction "VOUT_1_E2") (pintype "bidirectional"))
      (node (ref "IC9") (pin "E3") (pinfunction "VOUT_2_E3") (pintype "bidirectional"))
      (node (ref "J2") (pin "1") (pinfunction "1_1") (pintype "bidirectional"))
      (node (ref "Q1") (pin "2") (pinfunction "S_2") (pintype "bidirectional"))
      (node (ref "R17") (pin "1") (pinfunction "1_1") (pintype "bidirectional"))
      (node (ref "R18") (pin "1") (pinfunction "1_1") (pintype "bidirectional"))
      (node (ref "R5") (pin "2") (pinfunction "2_2") (pintype "bidirectional"))
      (node (ref "R7") (pin "2") (pinfunction "2_2") (pintype "bidirectional"))
      (node (ref "R8") (pin "2") (pinfunction "2_2") (pintype "bidirectional"))
      (node (ref "R_PWR_EPD") (pin "2") (pinfunction "2_2") (pintype "bidirectional"))
      (node (ref "TP5") (pin "TP") (pinfunction "TP_TP") (pintype "input"))
      (node (ref "TP_3V3") (pin "TP") (pinfunction "TP_TP") (pintype "input"))
      (node (ref "U1") (pin "P$A22") (pinfunction "VDD_P$A22") (pintype "power_in"))
      (node (ref "U1") (pin "P$AD14") (pinfunction "VDD_P$AD14") (pintype "power_in"))
      (node (ref "U1") (pin "P$AD23") (pinfunction "VDD_P$AD23") (pintype "power_in"))
      (node (ref "U1") (pin "P$B1") (pinfunction "VDD_P$B1") (pintype "power_in"))
      (node (ref "U1") (pin "P$W1") (pinfunction "VDD_P$W1") (pintype "power_in"))
      (node (ref "U1") (pin "P$Y2") (pinfunction "VDDH_P$Y2") (pintype "power_in"))
    )
    (net (code "2") (name "ALERT") (class "Default")
      (node (ref "U1") (pin "P$J24") (pinfunction "P0.10/NFC2_P$J24") (pintype "bidirectional"))
      (node (ref "U3") (pin "5") (pinfunction "~{ALERT}_5") (pintype "output"))
    )
    (net (code "3") (name "D+") (class "Default")
      (node (ref "D3") (pin "4") (pinfunction "I/O2_2_4") (pintype "bidirectional"))
      (node (ref "U1") (pin "P$AD6") (pinfunction "D+_P$AD6") (pintype "bidirectional"))
    )
    (net (code "4") (name "D-") (class "Default")
      (node (ref "D3") (pin "6") (pinfunction "I/O1_2_6") (pintype "bidirectional"))
      (node (ref "U1") (pin "P$AD4") (pinfunction "D-_P$AD4") (pintype "bidirectional"))
    )
    (net (code "5") (name "DN") (class "Default")
      (node (ref "D3") (pin "1") (pinfunction "I/O1_1_1") (pintype "bidirectional"))
      (node (ref "J4") (pin "A7") (pinfunction "DN1_A7") (pintype "bidirectional"))
      (node (ref "J4") (pin "B7") (pinfunction "DN2_B7") (pintype "bidirectional"))
    )
    (net (code "6") (name "DP") (class "Default")
      (node (ref "D3") (pin "3") (pinfunction "I/O2_1_3") (pintype "bidirectional"))
      (node (ref "J4") (pin "A6") (pinfunction "DP1_A6") (pintype "bidirectional"))
      (node (ref "J4") (pin "B6") (pinfunction "DP2_B6") (pintype "bidirectional"))
    )
    (net (code "7") (name "EPD_3V3") (class "Default")
      (node (ref "C1-EP-DR") (pin "1") (pinfunction "1_1") (pintype "passive"))
      (node (ref "EPD_C5") (pin "2") (pinfunction "2_2") (pintype "passive"))
      (node (ref "J1") (pin "15") (pinfunction "15_15") (pintype "bidirectional"))
      (node (ref "J1") (pin "16") (pinfunction "16_16") (pintype "bidirectional"))
      (node (ref "L5") (pin "2") (pinfunction "2_2") (pintype "passive"))
      (node (ref "Q1") (pin "3") (pinfunction "D_3") (pintype "bidirectional"))
    )
    (net (code "8") (name "EPD_BUSY") (class "Default")
      (node (ref "J1") (pin "9") (pinfunction "9_9") (pintype "bidirectional"))
      (node (ref "U1") (pin "P$AD12") (pinfunction "P0.17_P$AD12") (pintype "bidirectional"))
    )
    (net (code "9") (name "EPD_CS") (class "Default")
      (node (ref "J1") (pin "12") (pinfunction "12_12") (pintype "bidirectional"))
      (node (ref "U1") (pin "P$K2") (pinfunction "P0.05/AIN3_P$K2") (pintype "bidirectional"))
    )
    (net (code "10") (name "EPD_DC") (class "Default")
      (node (ref "J1") (pin "11") (pinfunction "11_11") (pintype "bidirectional"))
      (node (ref "U1") (pin "P$AD10") (pinfunction "P0.15_P$AD10") (pintype "bidirectional"))
    )
    (net (code "11") (name "EPD_RST") (class "Default")
      (node (ref "J1") (pin "10") (pinfunction "10_10") (pintype "bidirectional"))
      (node (ref "U1") (pin "P$AC11") (pinfunction "P0.16_P$AC11") (pintype "bidirectional"))
    )
    (net (code "12") (name "GDR") (class "Default")
      (node (ref "J1") (pin "2") (pinfunction "2_2") (pintype "bidirectional"))
      (node (ref "Q3") (pin "1") (pinfunction "G_1") (pintype "bidirectional"))
      (node (ref "R2_EP_DR") (pin "2") (pinfunction "2_2") (pintype "bidirectional"))
    )
    (net (code "13") (name "GND") (class "Default")
      (node (ref "C1") (pin "2") (pinfunction "2_2") (pintype "passive"))
      (node (ref "C1-EP-DR") (pin "2") (pinfunction "2_2") (pintype "passive"))
      (node (ref "C10") (pin "1") (pinfunction "1_1") (pintype "passive"))
      (node (ref "C11") (pin "2") (pinfunction "2_2") (pintype "passive"))
      (node (ref "C12") (pin "2") (pinfunction "2_2") (pintype "passive"))
      (node (ref "C13") (pin "1") (pinfunction "1_1") (pintype "passive"))
      (node (ref "C14") (pin "2") (pinfunction "2_2") (pintype "passive"))
      (node (ref "C15") (pin "2") (pinfunction "2_2") (pintype "passive"))
      (node (ref "C16") (pin "2") (pinfunction "2_2") (pintype "passive"))
      (node (ref "C17") (pin "1") (pinfunction "1_1") (pintype "passive"))
      (node (ref "C18") (pin "1") (pinfunction "1_1") (pintype "passive"))
      (node (ref "C19") (pin "2") (pinfunction "2_2") (pintype "passive"))
      (node (ref "C2") (pin "2") (pinfunction "2_2") (pintype "passive"))
      (node (ref "C20") (pin "2") (pinfunction "2_2") (pintype "passive"))
      (node (ref "C21") (pin "2") (pinfunction "2_2") (pintype "passive"))
      (node (ref "C22") (pin "2") (pinfunction "2_2") (pintype "passive"))
      (node (ref "C23") (pin "1") (pinfunction "1_1") (pintype "passive"))
      (node (ref "C24") (pin "1") (pinfunction "1_1") (pintype "passive"))
      (node (ref "C25") (pin "2") (pinfunction "2_2") (pintype "passive"))
      (node (ref "C27") (pin "2") (pinfunction "2_2") (pintype "passive"))
      (node (ref "C29") (pin "2") (pinfunction "2_2") (pintype "passive"))
      (node (ref "C3") (pin "2") (pinfunction "2_2") (pintype "passive"))
      (node (ref "C30") (pin "2") (pinfunction "2_2") (pintype "passive"))
      (node (ref "C31") (pin "2") (pinfunction "2_2") (pintype "passive"))
      (node (ref "C32") (pin "1") (pinfunction "1_1") (pintype "passive"))
      (node (ref "C33") (pin "2") (pinfunction "2_2") (pintype "passive"))
      (node (ref "C34") (pin "1") (pinfunction "1_1") (pintype "passive"))
      (node (ref "C37") (pin "1") (pinfunction "1_1") (pintype "passive"))
      (node (ref "C38") (pin "1") (pinfunction "1_1") (pintype "passive"))
      (node (ref "C39") (pin "2") (pinfunction "2_2") (pintype "passive"))
      (node (ref "C4") (pin "2") (pinfunction "2_2") (pintype "passive"))
      (node (ref "C42") (pin "2") (pinfunction "2_2") (pintype "passive"))
      (node (ref "C43") (pin "2") (pinfunction "2_2") (pintype "passive"))
      (node (ref "C5") (pin "2") (pinfunction "2_2") (pintype "passive"))
      (node (ref "C6") (pin "2") (pinfunction "2_2") (pintype "passive"))
      (node (ref "C7") (pin "2") (pinfunction "2_2") (pintype "passive"))
      (node (ref "C8") (pin "2") (pinfunction "2_2") (pintype "passive"))
      (node (ref "C9") (pin "2") (pinfunction "2_2") (pintype "passive"))
      (node (ref "D2") (pin "1") (pinfunction "K_1") (pintype "bidirectional"))
      (node (ref "D3") (pin "2") (pinfunction "GND_2") (pintype "bidirectional"))
      (node (ref "EPD_C1") (pin "1") (pinfunction "1_1") (pintype "passive"))
      (node (ref "EPD_C10") (pin "1") (pinfunction "1_1") (pintype "passive"))
      (node (ref "EPD_C11") (pin "1") (pinfunction "1_1") (pintype "passive"))
      (node (ref "EPD_C12") (pin "1") (pinfunction "1_1") (pintype "passive"))
      (node (ref "EPD_C2") (pin "1") (pinfunction "1_1") (pintype "passive"))
      (node (ref "EPD_C5") (pin "1") (pinfunction "1_1") (pintype "passive"))
      (node (ref "EPD_C6") (pin "1") (pinfunction "1_1") (pintype "passive"))
      (node (ref "EPD_C7") (pin "1") (pinfunction "1_1") (pintype "passive"))
      (node (ref "EPD_C8") (pin "1") (pinfunction "1_1") (pintype "passive"))
      (node (ref "EPD_C9") (pin "1") (pinfunction "1_1") (pintype "passive"))
      (node (ref "IC1") (pin "D2") (pinfunction "GND_D2") (pintype "bidirectional"))
      (node (ref "IC2") (pin "B1") (pinfunction "IN/TRIG_B1") (pintype "bidirectional"))
      (node (ref "IC2") (pin "B3") (pinfunction "GND_B3") (pintype "bidirectional"))
      (node (ref "IC3") (pin "8") (pinfunction "GNDIO_8") (pintype "bidirectional"))
      (node (ref "IC3") (pin "9") (pinfunction "GND_9") (pintype "bidirectional"))
      (node (ref "IC9") (pin "B1") (pinfunction "VSEL_B1") (pintype "bidirectional"))
      (node (ref "IC9") (pin "C1") (pinfunction "AGND_C1") (pintype "bidirectional"))
      (node (ref "IC9") (pin "C2") (pinfunction "PGND_1_C2") (pintype "bidirectional"))
      (node (ref "IC9") (pin "C3") (pinfunction "PGND_2_C3") (pintype "bidirectional"))
      (node (ref "J1") (pin "17") (pinfunction "17_17") (pintype "bidirectional"))
      (node (ref "J1") (pin "8") (pinfunction "8_8") (pintype "bidirectional"))
      (node (ref "J1") (pin "MP1") (pinfunction "MP1_MP1") (pintype "bidirectional"))
      (node (ref "J1") (pin "MP2") (pinfunction "MP2_MP2") (pintype "bidirectional"))
      (node (ref "J2") (pin "3") (pinfunction "3_3") (pintype "bidirectional"))
      (node (ref "J2") (pin "5") (pinfunction "5_5") (pintype "bidirectional"))
      (node (ref "J4") (pin "A12_B1") (pinfunction "GND_A12_B1") (pintype "power_in"))
      (node (ref "J4") (pin "A1_B12") (pinfunction "GND_A1_B12") (pintype "power_in"))
      (node (ref "J4") (pin "SH1") (pinfunction "SHIELD_SH1") (pintype "passive"))
      (node (ref "J4") (pin "SH2") (pinfunction "SHIELD_SH2") (pintype "passive"))
      (node (ref "J4") (pin "SH3") (pinfunction "SHIELD_SH3") (pintype "passive"))
      (node (ref "J4") (pin "SH4") (pinfunction "SHIELD_SH4") (pintype "passive"))
      (node (ref "R1_USB") (pin "1") (pinfunction "1_1") (pintype "bidirectional"))
      (node (ref "R2_EP_DR") (pin "1") (pinfunction "1_1") (pintype "bidirectional"))
      (node (ref "R2_USB") (pin "2") (pinfunction "2_2") (pintype "bidirectional"))
      (node (ref "R3") (pin "1") (pinfunction "1_1") (pintype "bidirectional"))
      (node (ref "R9") (pin "1") (pinfunction "1_1") (pintype "bidirectional"))
      (node (ref "R_TYPE_SEL") (pin "1") (pinfunction "1_1") (pintype "bidirectional"))
      (node (ref "SJ1") (pin "1") (pinfunction "1_1") (pintype "passive"))
      (node (ref "SW_DN") (pin "1") (pinfunction "1_1") (pintype "passive"))
      (node (ref "SW_ENT") (pin "1") (pinfunction "1_1") (pintype "passive"))
      (node (ref "SW_UP") (pin "1") (pinfunction "1_1") (pintype "passive"))
      (node (ref "TP6") (pin "TP") (pinfunction "TP_TP") (pintype "input"))
      (node (ref "TP_BAT_GND") (pin "TP") (pinfunction "TP_TP") (pintype "input"))
      (node (ref "U1") (pin "P$74") (pinfunction "VSS_PAD_P$74") (pintype "bidirectional"))
      (node (ref "U1") (pin "P$75") (pinfunction "VSS_PAD_P$75") (pintype "bidirectional"))
      (node (ref "U1") (pin "P$76") (pinfunction "VSS_PAD_P$76") (pintype "bidirectional"))
      (node (ref "U1") (pin "P$77") (pinfunction "VSS_PAD_P$77") (pintype "bidirectional"))
      (node (ref "U1") (pin "P$78") (pinfunction "VSS_PAD_P$78") (pintype "bidirectional"))
      (node (ref "U1") (pin "P$79") (pinfunction "VSS_PAD_P$79") (pintype "bidirectional"))
      (node (ref "U1") (pin "P$80") (pinfunction "VSS_PAD_P$80") (pintype "bidirectional"))
      (node (ref "U1") (pin "P$81") (pinfunction "VSS_PAD_P$81") (pintype "bidirectional"))
      (node (ref "U1") (pin "P$82") (pinfunction "VSS_PAD_P$82") (pintype "bidirectional"))
      (node (ref "U1") (pin "P$83") (pinfunction "VSS_PAD_P$83") (pintype "bidirectional"))
      (node (ref "U1") (pin "P$84") (pinfunction "VSS_PAD_P$84") (pintype "bidirectional"))
      (node (ref "U1") (pin "P$85") (pinfunction "VSS_PAD_P$85") (pintype "bidirectional"))
      (node (ref "U1") (pin "P$86") (pinfunction "VSS_PAD_P$86") (pintype "bidirectional"))
      (node (ref "U1") (pin "P$87") (pinfunction "VSS_PAD_P$87") (pintype "bidirectional"))
      (node (ref "U1") (pin "P$88") (pinfunction "VSS_PAD_P$88") (pintype "bidirectional"))
      (node (ref "U1") (pin "P$89") (pinfunction "VSS_PAD_P$89") (pintype "bidirectional"))
      (node (ref "U1") (pin "P$90") (pinfunction "VSS_PAD_P$90") (pintype "bidirectional"))
      (node (ref "U1") (pin "P$B7") (pinfunction "VSS_P$B7") (pintype "power_in"))
      (node (ref "U1") (pin "P$F23") (pinfunction "VSS_PA_P$F23") (pintype "bidirectional"))
      (node (ref "U3") (pin "1") (pinfunction "CTG_1") (pintype "power_in"))
      (node (ref "U3") (pin "4") (pinfunction "GND_4") (pintype "power_in"))
      (node (ref "U3") (pin "6") (pinfunction "QSTRT_6") (pintype "input"))
      (node (ref "U3") (pin "9") (pinfunction "EP_9") (pintype "power_in"))
      (node (ref "X1") (pin "2") (pinfunction "2_2") (pintype "passive"))
      (node (ref "X1") (pin "4") (pinfunction "4_4") (pintype "passive"))
    )
    (net (code "14") (name "HAPTIC_EN") (class "Default")
      (node (ref "IC2") (pin "A1") (pinfunction "EN_A1") (pintype "bidirectional"))
      (node (ref "U1") (pin "P$U1") (pinfunction "P0.12_P$U1") (pintype "bidirectional"))
    )
    (net (code "15") (name "IMU_INT1") (class "Default")
      (node (ref "IC3") (pin "5") (pinfunction "INT1_5") (pintype "bidirectional"))
      (node (ref "U1") (pin "P$N1") (pinfunction "P0.08_P$N1") (pintype "bidirectional"))
    )
    (net (code "16") (name "IMU_INT2") (class "Default")
      (node (ref "IC3") (pin "6") (pinfunction "INT2_6") (pintype "bidirectional"))
      (node (ref "U1") (pin "P$P2") (pinfunction "P1.08_P$P2") (pintype "bidirectional"))
    )
    (net (code "17") (name "LX1") (class "Default")
      (node (ref "IC9") (pin "B2") (pinfunction "SW1_1_B2") (pintype "bidirectional"))
      (node (ref "IC9") (pin "B3") (pinfunction "SW1_2_B3") (pintype "bidirectional"))
      (node (ref "L7") (pin "1") (pinfunction "1_1") (pintype "bidirectional"))
    )
    (net (code "18") (name "LX2") (class "Default")
      (node (ref "IC9") (pin "D2") (pinfunction "SW2_1_D2") (pintype "bidirectional"))
      (node (ref "IC9") (pin "D3") (pinfunction "SW2_2_D3") (pintype "bidirectional"))
      (node (ref "L7") (pin "2") (pinfunction "2_2") (pintype "bidirectional"))
    )
    (net (code "19") (name "MOSI") (class "Default")
      (node (ref "J1") (pin "14") (pinfunction "14_14") (pintype "bidirectional"))
      (node (ref "U1") (pin "P$B13") (pinfunction "P0.03/AIN1_P$B13") (pintype "bidirectional"))
    )
    (net (code "20") (name "Net-(ANT1-FEED)") (class "Default")
      (node (ref "ANT1") (pin "1") (pinfunction "FEED_1") (pintype "input"))
      (node (ref "C22") (pin "1") (pinfunction "1_1") (pintype "passive"))
      (node (ref "C4") (pin "1") (pinfunction "1_1") (pintype "passive"))
      (node (ref "L1") (pin "2") (pinfunction "2_2") (pintype "passive"))
    )
    (net (code "21") (name "Net-(D2-A)") (class "Default")
      (node (ref "C2-EP-DR1") (pin "1") (pinfunction "1_1") (pintype "passive"))
      (node (ref "D2") (pin "2") (pinfunction "A_2") (pintype "bidirectional"))
      (node (ref "D4") (pin "1") (pinfunction "K_1") (pintype "bidirectional"))
    )
    (net (code "22") (name "Net-(D5-A)") (class "Default")
      (node (ref "C2-EP-DR1") (pin "2") (pinfunction "2_2") (pintype "passive"))
      (node (ref "D5") (pin "2") (pinfunction "A_2") (pintype "bidirectional"))
      (node (ref "L5") (pin "1") (pinfunction "1_1") (pintype "passive"))
      (node (ref "Q3") (pin "3") (pinfunction "D_3") (pintype "bidirectional"))
    )
    (net (code "23") (name "Net-(EPD_C1-Pad2)") (class "Default")
      (node (ref "EPD_C1") (pin "2") (pinfunction "2_2") (pintype "passive"))
      (node (ref "J1") (pin "5") (pinfunction "5_5") (pintype "bidirectional"))
    )
    (net (code "24") (name "Net-(EPD_C2-Pad2)") (class "Default")
      (node (ref "EPD_C2") (pin "2") (pinfunction "2_2") (pintype "passive"))
      (node (ref "J1") (pin "4") (pinfunction "4_4") (pintype "bidirectional"))
    )
    (net (code "25") (name "Net-(EPD_C6-Pad2)") (class "Default")
      (node (ref "EPD_C6") (pin "2") (pinfunction "2_2") (pintype "passive"))
      (node (ref "J1") (pin "18") (pinfunction "18_18") (pintype "bidirectional"))
    )
    (net (code "26") (name "Net-(EPD_C7-Pad2)") (class "Default")
      (node (ref "EPD_C7") (pin "2") (pinfunction "2_2") (pintype "passive"))
      (node (ref "J1") (pin "19") (pinfunction "19_19") (pintype "bidirectional"))
    )
    (net (code "27") (name "Net-(EPD_C8-Pad2)") (class "Default")
      (node (ref "EPD_C8") (pin "2") (pinfunction "2_2") (pintype "passive"))
      (node (ref "J1") (pin "20") (pinfunction "20_20") (pintype "bidirectional"))
    )
    (net (code "28") (name "Net-(EPD_C11-Pad2)") (class "Default")
      (node (ref "EPD_C11") (pin "2") (pinfunction "2_2") (pintype "passive"))
      (node (ref "J1") (pin "23") (pinfunction "23_23") (pintype "bidirectional"))
    )
    (net (code "29") (name "Net-(EPD_C12-Pad2)") (class "Default")
      (node (ref "EPD_C12") (pin "2") (pinfunction "2_2") (pintype "passive"))
      (node (ref "J1") (pin "24") (pinfunction "24_24") (pintype "bidirectional"))
    )
    (net (code "30") (name "Net-(IC1-TS{slash}MR)") (class "Default")
      (node (ref "IC1") (pin "D1") (pinfunction "TS/MR_D1") (pintype "bidirectional"))
      (node (ref "R9") (pin "2") (pinfunction "2_2") (pintype "bidirectional"))
    )
    (net (code "31") (name "Net-(IC2-REG)") (class "Default")
      (node (ref "C32") (pin "2") (pinfunction "2_2") (pintype "passive"))
      (node (ref "IC2") (pin "A2") (pinfunction "REG_A2") (pintype "bidirectional"))
    )
    (net (code "32") (name "Net-(IC3-SDO)") (class "Default")
      (node (ref "IC3") (pin "1") (pinfunction "SDO_1") (pintype "bidirectional"))
      (node (ref "R3") (pin "2") (pinfunction "2_2") (pintype "bidirectional"))
    )
    (net (code "33") (name "Net-(IC9-SCL)") (class "Default")
      (node (ref "IC9") (pin "D1") (pinfunction "SCL_D1") (pintype "bidirectional"))
      (node (ref "R4") (pin "2") (pinfunction "2_2") (pintype "bidirectional"))
    )
    (net (code "34") (name "Net-(IC9-SDA)") (class "Default")
      (node (ref "IC9") (pin "E1") (pinfunction "SDA_E1") (pintype "bidirectional"))
      (node (ref "R2") (pin "2") (pinfunction "2_2") (pintype "bidirectional"))
    )
    (net (code "35") (name "Net-(J4-CC1)") (class "Default")
      (node (ref "J4") (pin "A5") (pinfunction "CC1_A5") (pintype "bidirectional"))
      (node (ref "R1_USB") (pin "2") (pinfunction "2_2") (pintype "bidirectional"))
    )
    (net (code "36") (name "Net-(J4-CC2)") (class "Default")
      (node (ref "J4") (pin "B5") (pinfunction "CC2_B5") (pintype "bidirectional"))
      (node (ref "R2_USB") (pin "1") (pinfunction "1_1") (pintype "bidirectional"))
    )
    (net (code "37") (name "Net-(L2-Pad1)") (class "Default")
      (node (ref "L2") (pin "1") (pinfunction "1_1") (pintype "passive"))
      (node (ref "L3") (pin "2") (pinfunction "2_2") (pintype "passive"))
    )
    (net (code "38") (name "Net-(R1_EP_DR-Pad1)") (class "Default")
      (node (ref "R1_EP_DR") (pin "1") (pinfunction "1_1") (pintype "bidirectional"))
      (node (ref "R_TYPE_SEL") (pin "2") (pinfunction "2_2") (pintype "bidirectional"))
      (node (ref "SJ1") (pin "2") (pinfunction "2_2") (pintype "passive"))
    )
    (net (code "39") (name "Net-(U1-ANT)") (class "Default")
      (node (ref "C3") (pin "1") (pinfunction "1_1") (pintype "passive"))
      (node (ref "L1") (pin "1") (pinfunction "1_1") (pintype "passive"))
      (node (ref "U1") (pin "P$H23") (pinfunction "ANT_P$H23") (pintype "bidirectional"))
    )
    (net (code "40") (name "Net-(U1-DCC)") (class "Default")
      (node (ref "L2") (pin "2") (pinfunction "2_2") (pintype "passive"))
      (node (ref "U1") (pin "P$B3") (pinfunction "DCC_P$B3") (pintype "output"))
    )
    (net (code "41") (name "Net-(U1-DEC1)") (class "Default")
      (node (ref "C5") (pin "1") (pinfunction "1_1") (pintype "passive"))
      (node (ref "U1") (pin "P$C1") (pinfunction "DEC1_P$C1") (pintype "power_in"))
    )
    (net (code "42") (name "Net-(U1-DEC2)") (class "Default")
      (node (ref "C13") (pin "2") (pinfunction "2_2") (pintype "passive"))
      (node (ref "U1") (pin "P$A18") (pinfunction "DEC2_P$A18") (pintype "bidirectional"))
    )
    (net (code "43") (name "Net-(U1-DEC3)") (class "Default")
      (node (ref "C11") (pin "1") (pinfunction "1_1") (pintype "passive"))
      (node (ref "U1") (pin "P$D23") (pinfunction "DEC3_P$D23") (pintype "bidirectional"))
    )
    (net (code "44") (name "Net-(U1-DEC3V3)") (class "Default")
      (node (ref "C20") (pin "1") (pinfunction "1_1") (pintype "passive"))
      (node (ref "U1") (pin "P$AC5") (pinfunction "DEC3V3_P$AC5") (pintype "bidirectional"))
    )
    (net (code "45") (name "Net-(U1-DEC4)") (class "Default")
      (node (ref "C10") (pin "2") (pinfunction "2_2") (pintype "passive"))
      (node (ref "C15") (pin "1") (pinfunction "1_1") (pintype "passive"))
      (node (ref "C16") (pin "1") (pinfunction "1_1") (pintype "passive"))
      (node (ref "L3") (pin "1") (pinfunction "1_1") (pintype "passive"))
      (node (ref "U1") (pin "P$B5") (pinfunction "DEC4_P$B5") (pintype "power_in"))
      (node (ref "U1") (pin "P$E24") (pinfunction "DEC6_P$E24") (pintype "bidirectional"))
    )
    (net (code "46") (name "Net-(U1-DEC5)") (class "Default")
      (node (ref "C9") (pin "1") (pinfunction "1_1") (pintype "passive"))
      (node (ref "U1") (pin "P$N24") (pinfunction "DEC5_P$N24") (pintype "bidirectional"))
    )
    (net (code "47") (name "Net-(U1-P0.00{slash}XL1)") (class "Default")
      (node (ref "C17") (pin "2") (pinfunction "2_2") (pintype "passive"))
      (node (ref "U1") (pin "P$D2") (pinfunction "P0.00/XL1_P$D2") (pintype "bidirectional"))
      (node (ref "X2") (pin "2") (pinfunction "2_2") (pintype "passive"))
    )
    (net (code "48") (name "Net-(U1-P0.01{slash}XL2)") (class "Default")
      (node (ref "C18") (pin "2") (pinfunction "2_2") (pintype "passive"))
      (node (ref "U1") (pin "P$F2") (pinfunction "P0.01/XL2_P$F2") (pintype "bidirectional"))
      (node (ref "X2") (pin "1") (pinfunction "1_1") (pintype "passive"))
    )
    (net (code "49") (name "Net-(U1-XC1)") (class "Default")
      (node (ref "C1") (pin "1") (pinfunction "1_1") (pintype "passive"))
      (node (ref "U1") (pin "P$B24") (pinfunction "XC1_P$B24") (pintype "input"))
      (node (ref "X1") (pin "1") (pinfunction "1_1") (pintype "passive"))
    )
    (net (code "50") (name "Net-(U1-XC2)") (class "Default")
      (node (ref "C2") (pin "1") (pinfunction "1_1") (pintype "passive"))
      (node (ref "U1") (pin "P$A23") (pinfunction "XC2_P$A23") (pintype "output"))
      (node (ref "X1") (pin "3") (pinfunction "3_3") (pintype "passive"))
    )
    (net (code "51") (name "OUT+") (class "Default")
      (node (ref "IC2") (pin "A3") (pinfunction "OUT+_A3") (pintype "bidirectional"))
      (node (ref "TP_OP") (pin "TP") (pinfunction "TP_TP") (pintype "input"))
    )
    (net (code "52") (name "OUT-") (class "Default")
      (node (ref "IC2") (pin "C3") (pinfunction "OUT-_C3") (pintype "bidirectional"))
      (node (ref "TP_ON") (pin "TP") (pinfunction "TP_TP") (pintype "input"))
    )
    (net (code "53") (name "P0.04") (class "Default")
      (node (ref "U1") (pin "P$J1") (pinfunction "P0.04/AIN2_P$J1") (pintype "bidirectional"))
    )
    (net (code "54") (name "P0.09") (class "Default")
      (node (ref "U1") (pin "P$L24") (pinfunction "P0.09/NFC1_P$L24") (pintype "bidirectional"))
    )
    (net (code "55") (name "P0.13") (class "Default")
      (node (ref "C30") (pin "1") (pinfunction "1_1") (pintype "passive"))
      (node (ref "R5") (pin "1") (pinfunction "1_1") (pintype "bidirectional"))
      (node (ref "SW_UP") (pin "2") (pinfunction "2_2") (pintype "passive"))
      (node (ref "U1") (pin "P$AD8") (pinfunction "P0.13_P$AD8") (pintype "bidirectional"))
    )
    (net (code "56") (name "P0.14") (class "Default")
      (node (ref "C31") (pin "1") (pinfunction "1_1") (pintype "passive"))
      (node (ref "R8") (pin "1") (pinfunction "1_1") (pintype "bidirectional"))
      (node (ref "SW_ENT") (pin "2") (pinfunction "2_2") (pintype "passive"))
      (node (ref "U1") (pin "P$AC9") (pinfunction "P0.14_P$AC9") (pintype "bidirectional"))
    )
    (net (code "57") (name "P0.19") (class "Default")
      (node (ref "U1") (pin "P$AC15") (pinfunction "P0.19_P$AC15") (pintype "bidirectional"))
    )
    (net (code "58") (name "P0.20") (class "Default")
      (node (ref "U1") (pin "P$AD16") (pinfunction "P0.20_P$AD16") (pintype "bidirectional"))
    )
    (net (code "59") (name "P0.21") (class "Default")
      (node (ref "U1") (pin "P$AC17") (pinfunction "P0.21_P$AC17") (pintype "bidirectional"))
    )
    (net (code "60") (name "P0.22") (class "Default")
      (node (ref "U1") (pin "P$AD18") (pinfunction "P0.22_P$AD18") (pintype "bidirectional"))
    )
    (net (code "61") (name "P0.23") (class "Default")
      (node (ref "U1") (pin "P$AC19") (pinfunction "P0.23_P$AC19") (pintype "bidirectional"))
    )
    (net (code "62") (name "P0.24") (class "Default")
      (node (ref "U1") (pin "P$AD20") (pinfunction "P0.24_P$AD20") (pintype "bidirectional"))
    )
    (net (code "63") (name "P0.25") (class "Default")
      (node (ref "U1") (pin "P$AC21") (pinfunction "P0.25_P$AC21") (pintype "bidirectional"))
    )
    (net (code "64") (name "P0.26") (class "Default")
      (node (ref "U1") (pin "P$G1") (pinfunction "P0.26_P$G1") (pintype "bidirectional"))
    )
    (net (code "65") (name "P0.27") (class "Default")
      (node (ref "U1") (pin "P$H2") (pinfunction "P0.27_P$H2") (pintype "bidirectional"))
    )
    (net (code "66") (name "P0.28") (class "Default")
      (node (ref "U1") (pin "P$B11") (pinfunction "P0.28/AIN4_P$B11") (pintype "bidirectional"))
    )
    (net (code "67") (name "P0.29") (class "Default")
      (node (ref "U1") (pin "P$A10") (pinfunction "P0.29/AIN5_P$A10") (pintype "bidirectional"))
    )
    (net (code "68") (name "P0.30") (class "Default")
      (node (ref "U1") (pin "P$B9") (pinfunction "P0.30/AIN6_P$B9") (pintype "bidirectional"))
    )
    (net (code "69") (name "P0.31") (class "Default")
      (node (ref "U1") (pin "P$A8") (pinfunction "P0.31/AIN7_P$A8") (pintype "bidirectional"))
    )
    (net (code "70") (name "P1.01") (class "Default")
      (node (ref "Q1") (pin "1") (pinfunction "G_1") (pintype "bidirectional"))
      (node (ref "R_PWR_EPD") (pin "1") (pinfunction "1_1") (pintype "bidirectional"))
      (node (ref "U1") (pin "P$Y23") (pinfunction "P1.01_P$Y23") (pintype "bidirectional"))
    )
    (net (code "71") (name "P1.02") (class "Default")
      (node (ref "C29") (pin "1") (pinfunction "1_1") (pintype "passive"))
      (node (ref "R7") (pin "1") (pinfunction "1_1") (pintype "bidirectional"))
      (node (ref "SW_DN") (pin "2") (pinfunction "2_2") (pintype "passive"))
      (node (ref "U1") (pin "P$W24") (pinfunction "P1.02_P$W24") (pintype "bidirectional"))
    )
    (net (code "72") (name "P1.03") (class "Default")
      (node (ref "U1") (pin "P$V23") (pinfunction "P1.03_P$V23") (pintype "bidirectional"))
    )
    (net (code "73") (name "P1.04") (class "Default")
      (node (ref "U1") (pin "P$U24") (pinfunction "P1.04_P$U24") (pintype "bidirectional"))
    )
    (net (code "74") (name "P1.05") (class "Default")
      (node (ref "U1") (pin "P$T23") (pinfunction "P1.05_P$T23") (pintype "bidirectional"))
    )
    (net (code "75") (name "P1.06") (class "Default")
      (node (ref "U1") (pin "P$R24") (pinfunction "P1.06_P$R24") (pintype "bidirectional"))
    )
    (net (code "76") (name "P1.07") (class "Default")
      (node (ref "U1") (pin "P$P23") (pinfunction "P1.07_P$P23") (pintype "bidirectional"))
    )
    (net (code "77") (name "P1.09") (class "Default")
      (node (ref "U1") (pin "P$R1") (pinfunction "P1.09_P$R1") (pintype "bidirectional"))
    )
    (net (code "78") (name "P1.10") (class "Default")
      (node (ref "U1") (pin "P$A20") (pinfunction "P1.10_P$A20") (pintype "bidirectional"))
    )
    (net (code "79") (name "P1.11") (class "Default")
      (node (ref "U1") (pin "P$B19") (pinfunction "P1.11_P$B19") (pintype "bidirectional"))
    )
    (net (code "80") (name "P1.12") (class "Default")
      (node (ref "U1") (pin "P$B17") (pinfunction "P1.12_P$B17") (pintype "bidirectional"))
    )
    (net (code "81") (name "P1.13") (class "Default")
      (node (ref "U1") (pin "P$A16") (pinfunction "P1.13_P$A16") (pintype "bidirectional"))
    )
    (net (code "82") (name "P1.14") (class "Default")
      (node (ref "U1") (pin "P$B15") (pinfunction "P1.14_P$B15") (pintype "bidirectional"))
    )
    (net (code "83") (name "P1.15") (class "Default")
      (node (ref "U1") (pin "P$A14") (pinfunction "P1.15_P$A14") (pintype "bidirectional"))
    )
    (net (code "84") (name "PMIC_INT") (class "Default")
      (node (ref "IC1") (pin "A1") (pinfunction "~{INT}_A1") (pintype "bidirectional"))
      (node (ref "U1") (pin "P$T2") (pinfunction "P0.11_P$T2") (pintype "bidirectional"))
    )
    (net (code "85") (name "PREVGH") (class "Default")
      (node (ref "D5") (pin "1") (pinfunction "K_1") (pintype "bidirectional"))
      (node (ref "EPD_C9") (pin "2") (pinfunction "2_2") (pintype "passive"))
      (node (ref "J1") (pin "21") (pinfunction "21_21") (pintype "bidirectional"))
    )
    (net (code "86") (name "PREVGL") (class "Default")
      (node (ref "D4") (pin "2") (pinfunction "A_2") (pintype "bidirectional"))
      (node (ref "EPD_C10") (pin "2") (pinfunction "2_2") (pintype "passive"))
      (node (ref "J1") (pin "22") (pinfunction "22_22") (pintype "bidirectional"))
    )
    (net (code "87") (name "RESE") (class "Default")
      (node (ref "J1") (pin "3") (pinfunction "3_3") (pintype "bidirectional"))
      (node (ref "Q3") (pin "2") (pinfunction "S_2") (pintype "bidirectional"))
      (node (ref "R1_EP_DR") (pin "2") (pinfunction "2_2") (pintype "bidirectional"))
    )
    (net (code "88") (name "RESET") (class "Default")
      (node (ref "J2") (pin "6") (pinfunction "6_6") (pintype "bidirectional"))
      (node (ref "TP4") (pin "TP") (pinfunction "TP_TP") (pintype "input"))
      (node (ref "U1") (pin "P$AC13") (pinfunction "P0.18/RESET_P$AC13") (pintype "bidirectional"))
    )
    (net (code "89") (name "SCK") (class "Default")
      (node (ref "J1") (pin "13") (pinfunction "13_13") (pintype "bidirectional"))
      (node (ref "U1") (pin "P$A12") (pinfunction "P0.02/AIN0_P$A12") (pintype "bidirectional"))
    )
    (net (code "90") (name "SCL") (class "Default")
      (node (ref "IC1") (pin "B1") (pinfunction "SCL_B1") (pintype "bidirectional"))
      (node (ref "IC2") (pin "C1") (pinfunction "SCL_C1") (pintype "bidirectional"))
      (node (ref "IC3") (pin "12") (pinfunction "SCX_12") (pintype "bidirectional"))
      (node (ref "R17") (pin "2") (pinfunction "2_2") (pintype "bidirectional"))
      (node (ref "R4") (pin "1") (pinfunction "1_1") (pintype "bidirectional"))
      (node (ref "TP_SCL") (pin "TP") (pinfunction "TP_TP") (pintype "input"))
      (node (ref "U1") (pin "P$M2") (pinfunction "P0.07_P$M2") (pintype "bidirectional"))
      (node (ref "U3") (pin "7") (pinfunction "SCL_7") (pintype "input"))
    )
    (net (code "91") (name "SDA") (class "Default")
      (node (ref "IC1") (pin "C1") (pinfunction "SDA_C1") (pintype "bidirectional"))
      (node (ref "IC2") (pin "B2") (pinfunction "SDA_B2") (pintype "bidirectional"))
      (node (ref "IC3") (pin "2") (pinfunction "SDX_2") (pintype "bidirectional"))
      (node (ref "R18") (pin "2") (pinfunction "2_2") (pintype "bidirectional"))
      (node (ref "R2") (pin "1") (pinfunction "1_1") (pintype "bidirectional"))
      (node (ref "TP_SDA") (pin "TP") (pinfunction "TP_TP") (pintype "input"))
      (node (ref "U1") (pin "P$L1") (pinfunction "P0.06_P$L1") (pintype "bidirectional"))
      (node (ref "U3") (pin "8") (pinfunction "SDA_8") (pintype "bidirectional"))
    )
    (net (code "92") (name "SWDCLK") (class "Default")
      (node (ref "J2") (pin "4") (pinfunction "4_4") (pintype "bidirectional"))
      (node (ref "TP3") (pin "TP") (pinfunction "TP_TP") (pintype "input"))
      (node (ref "U1") (pin "P$AA24") (pinfunction "SWDCLK_P$AA24") (pintype "input"))
    )
    (net (code "93") (name "SWDIO") (class "Default")
      (node (ref "J2") (pin "2") (pinfunction "2_2") (pintype "bidirectional"))
      (node (ref "TP2") (pin "TP") (pinfunction "TP_TP") (pintype "input"))
      (node (ref "U1") (pin "P$AC24") (pinfunction "SWDIO_P$AC24") (pintype "bidirectional"))
    )
    (net (code "94") (name "SWO") (class "Default")
      (node (ref "TP1") (pin "TP") (pinfunction "TP_TP") (pintype "input"))
      (node (ref "U1") (pin "P$AD22") (pinfunction "P1.00_P$AD22") (pintype "bidirectional"))
    )
    (net (code "95") (name "VBAT") (class "Default")
      (node (ref "C27") (pin "1") (pinfunction "1_1") (pintype "passive"))
      (node (ref "C37") (pin "2") (pinfunction "2_2") (pintype "passive"))
      (node (ref "IC1") (pin "C2") (pinfunction "BAT_C2") (pintype "bidirectional"))
      (node (ref "TP_VBAT") (pin "TP") (pinfunction "TP_TP") (pintype "input"))
      (node (ref "U3") (pin "2") (pinfunction "CELL_2") (pintype "power_in"))
      (node (ref "U3") (pin "3") (pinfunction "VDD_3") (pintype "power_in"))
    )
    (net (code "96") (name "VBUS") (class "Default")
      (node (ref "C21") (pin "1") (pinfunction "1_1") (pintype "passive"))
      (node (ref "C38") (pin "2") (pinfunction "2_2") (pintype "passive"))
      (node (ref "C42") (pin "1") (pinfunction "1_1") (pintype "passive"))
      (node (ref "C43") (pin "1") (pinfunction "1_1") (pintype "passive"))
      (node (ref "D3") (pin "5") (pinfunction "VBUS_5") (pintype "bidirectional"))
      (node (ref "IC1") (pin "A2") (pinfunction "IN_A2") (pintype "bidirectional"))
      (node (ref "J4") (pin "A4_B9") (pinfunction "VBUS_A4_B9") (pintype "power_in"))
      (node (ref "J4") (pin "A9_B4") (pinfunction "VBUS_A9_B4") (pintype "power_in"))
      (node (ref "U1") (pin "P$AD2") (pinfunction "VBUS_P$AD2") (pintype "power_in"))
    )
    (net (code "97") (name "VREG") (class "Default")
      (node (ref "C23") (pin "2") (pinfunction "2_2") (pintype "passive"))
      (node (ref "C24") (pin "2") (pinfunction "2_2") (pintype "passive"))
      (node (ref "C39") (pin "1") (pinfunction "1_1") (pintype "passive"))
      (node (ref "IC1") (pin "B2") (pinfunction "SYS_B2") (pintype "bidirectional"))
      (node (ref "IC9") (pin "A1") (pinfunction "EN_A1") (pintype "bidirectional"))
      (node (ref "IC9") (pin "A2") (pinfunction "VIN_1_A2") (pintype "bidirectional"))
      (node (ref "IC9") (pin "A3") (pinfunction "VIN_2_A3") (pintype "bidirectional"))
      (node (ref "TP_VREG") (pin "TP") (pinfunction "TP_TP") (pintype "input"))
    )
    (net (code "98") (name "unconnected-(ANT1-NC-Pad2)") (class "Default")
      (node (ref "ANT1") (pin "2") (pinfunction "NC_2") (pintype "no_connect"))
    )
    (net (code "99") (name "unconnected-(IC3-ASCL-Pad11)") (class "Default")
      (node (ref "IC3") (pin "11") (pinfunction "ASCL_11") (pintype "bidirectional"))
    )
    (net (code "100") (name "unconnected-(IC3-ASDA-Pad4)") (class "Default")
      (node (ref "IC3") (pin "4") (pinfunction "ASDA_4") (pintype "bidirectional"))
    )
    (net (code "101") (name "unconnected-(J1-Pad1)") (class "Default")
      (node (ref "J1") (pin "1") (pinfunction "1_1") (pintype "bidirectional"))
    )
    (net (code "102") (name "unconnected-(J1-Pad6)") (class "Default")
      (node (ref "J1") (pin "6") (pinfunction "6_6") (pintype "bidirectional"))
    )
    (net (code "103") (name "unconnected-(J1-Pad7)") (class "Default")
      (node (ref "J1") (pin "7") (pinfunction "7_7") (pintype "bidirectional"))
    )
    (net (code "104") (name "unconnected-(J4-SBU1-PadA8)") (class "Default")
      (node (ref "J4") (pin "A8") (pinfunction "SBU1_A8") (pintype "bidirectional"))
    )
    (net (code "105") (name "unconnected-(J4-SBU2-PadB8)") (class "Default")
      (node (ref "J4") (pin "B8") (pinfunction "SBU2_B8") (pintype "bidirectional"))
    )
    (net (code "106") (name "unconnected-(U1-DCCH-PadP$AB2)") (class "Default")
      (node (ref "U1") (pin "P$AB2") (pinfunction "DCCH_P$AB2") (pintype "bidirectional"))
    )
  )
)
